# Sheet2.net
KiCad netlist of a schematic drawn in Altium Designer
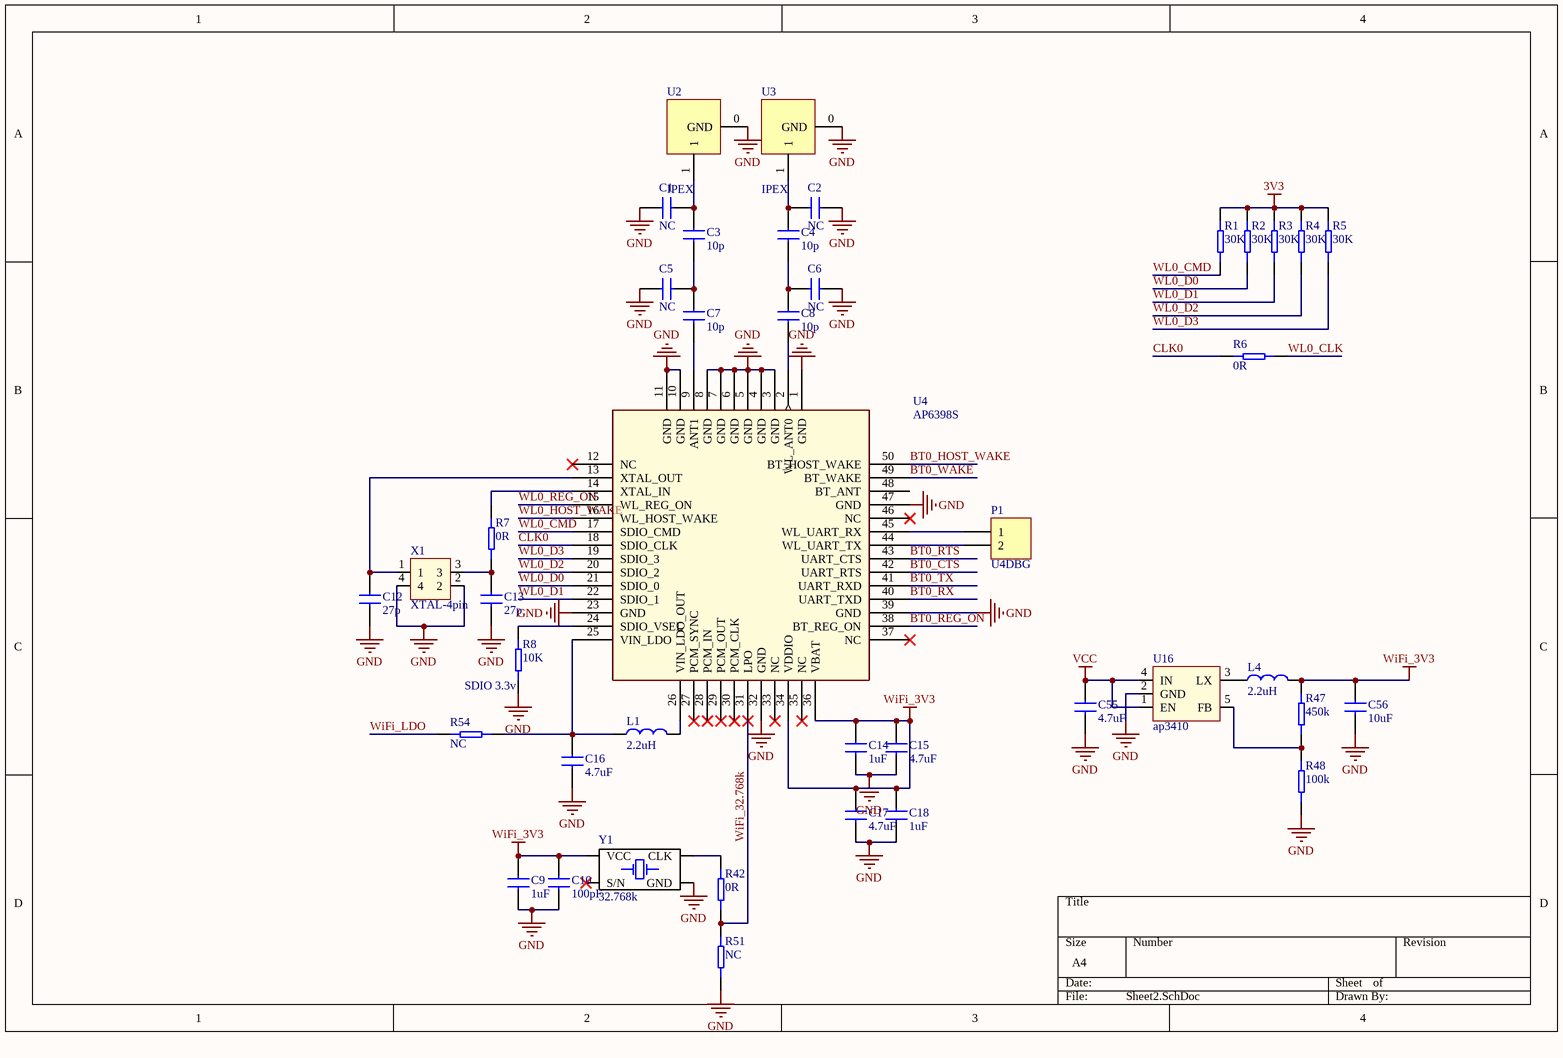
[diagram p0: Sheet2.SchDoc]

(export (version "E")
  (design (tool "Eeschema 10.0.6"))
  (components
    (comp (ref "C1")
      (value "NC")
      (footprint "0402C")
      (description "SMD-CAP")
      (libsource (lib "Zero") (part "CAP"))
    )
    (comp (ref "C2")
      (value "NC")
      (footprint "0402C")
      (description "SMD-CAP")
      (libsource (lib "Zero") (part "CAP"))
    )
    (comp (ref "C3")
      (value "10p")
      (footprint "0402C")
      (description "SMD-CAP")
      (libsource (lib "Zero") (part "CAP"))
    )
    (comp (ref "C4")
      (value "10p")
      (footprint "0402C")
      (description "SMD-CAP")
      (libsource (lib "Zero") (part "CAP"))
    )
    (comp (ref "C5")
      (value "NC")
      (footprint "0402C")
      (description "SMD-CAP")
      (libsource (lib "Zero") (part "CAP"))
    )
    (comp (ref "C6")
      (value "NC")
      (footprint "0402C")
      (description "SMD-CAP")
      (libsource (lib "Zero") (part "CAP"))
    )
    (comp (ref "C7")
      (value "10p")
      (footprint "0402C")
      (description "SMD-CAP")
      (libsource (lib "Zero") (part "CAP"))
    )
    (comp (ref "C8")
      (value "10p")
      (footprint "0402C")
      (description "SMD-CAP")
      (libsource (lib "Zero") (part "CAP"))
    )
    (comp (ref "C9")
      (value "1uF")
      (footprint "0402C")
      (description "SMD-CAP")
      (libsource (lib "Zero") (part "CAP"))
    )
    (comp (ref "C10")
      (value "100pF")
      (footprint "0402C")
      (description "SMD-CAP")
      (libsource (lib "Zero") (part "CAP"))
    )
    (comp (ref "C12")
      (value "27p")
      (footprint "0402C")
      (description "SMD-CAP")
      (libsource (lib "Zero") (part "CAP"))
    )
    (comp (ref "C13")
      (value "27p")
      (footprint "0402C")
      (description "SMD-CAP")
      (libsource (lib "Zero") (part "CAP"))
    )
    (comp (ref "C14")
      (value "1uF")
      (footprint "0402C")
      (description "SMD-CAP")
      (libsource (lib "Zero") (part "CAP"))
    )
    (comp (ref "C15")
      (value "4.7uF")
      (footprint "0402C")
      (description "SMD-CAP")
      (libsource (lib "Zero") (part "CAP"))
    )
    (comp (ref "C16")
      (value "4.7uF")
      (footprint "0603C")
      (description "SMD-CAP")
      (libsource (lib "Zero") (part "CAP"))
    )
    (comp (ref "C17")
      (value "4.7uF")
      (footprint "0402C")
      (description "SMD-CAP")
      (libsource (lib "Zero") (part "CAP"))
    )
    (comp (ref "C18")
      (value "1uF")
      (footprint "0402C")
      (description "SMD-CAP")
      (libsource (lib "Zero") (part "CAP"))
    )
    (comp (ref "C55")
      (value "4.7uF")
      (footprint "0603C")
      (description "SMD-CAP")
      (libsource (lib "Zero") (part "CAP"))
    )
    (comp (ref "C56")
      (value "10uF")
      (footprint "0603C")
      (description "SMD-CAP")
      (libsource (lib "Zero") (part "CAP"))
    )
    (comp (ref "L1")
      (value "2.2uH")
      (footprint "0805R")
      (description "LQM2MPN2R2NG0L")
      (libsource (lib "Zero") (part "L1"))
    )
    (comp (ref "L4")
      (value "2.2uH")
      (footprint "0805R")
      (description "LQM2MPN3R3NG0L")
      (libsource (lib "Zero") (part "L1"))
    )
    (comp (ref "P1")
      (value "U4DBG")
      (footprint "MHDR1X2")
      (description "Header, 2-Pin")
      (fields (field (name "PUBLISHER") "Altium Limited"))
      (libsource (lib "Miscellaneous Connectors") (part "MHDR1X2"))
    )
    (comp (ref "R1") (value "30K") (footprint "0402R") (libsource (lib "Zero") (part "R")))
    (comp (ref "R2") (value "30K") (footprint "0402R") (libsource (lib "Zero") (part "R")))
    (comp (ref "R3") (value "30K") (footprint "0402R") (libsource (lib "Zero") (part "R")))
    (comp (ref "R4") (value "30K") (footprint "0402R") (libsource (lib "Zero") (part "R")))
    (comp (ref "R5") (value "30K") (footprint "0402R") (libsource (lib "Zero") (part "R")))
    (comp (ref "R6") (value "0R") (footprint "0402R") (libsource (lib "Zero") (part "R")))
    (comp (ref "R7") (value "0R") (footprint "0402R") (libsource (lib "Zero") (part "R")))
    (comp (ref "R8") (value "10K") (footprint "0402R") (libsource (lib "Zero") (part "R")))
    (comp (ref "R42") (value "0R") (footprint "0402R") (libsource (lib "Zero") (part "R")))
    (comp (ref "R47") (value "450k") (footprint "0402R") (libsource (lib "Zero") (part "R")))
    (comp (ref "R48") (value "100k") (footprint "0402R") (libsource (lib "Zero") (part "R")))
    (comp (ref "R51") (value "NC") (footprint "0402R") (libsource (lib "Zero") (part "R")))
    (comp (ref "R54") (value "NC") (footprint "0805R") (libsource (lib "Zero") (part "R")))
    (comp (ref "U2") (value "IPEX") (footprint "IPEX") (libsource (lib "Zero") (part "IPEX")))
    (comp (ref "U3") (value "IPEX") (footprint "IPEX") (libsource (lib "Zero") (part "IPEX")))
    (comp (ref "U4")
      (value "AP6398S")
      (footprint "ap6398sr3")
      (libsource (lib "20180125H1") (part "AP6398S"))
    )
    (comp (ref "U16")
      (value "ap3410")
      (footprint "LC-SOT-23-5")
      (libsource (lib "20180125H1") (part "ap3410"))
    )
    (comp (ref "X1")
      (value "XTAL-4pin")
      (footprint "LC-SMD-3225_4P")
      (description "37.4MHz")
      (libsource (lib "20180125H1") (part "XTAL-4pin"))
    )
    (comp (ref "Y1")
      (value "32.768k")
      (footprint "3225")
      (description "3225 有源")
      (libsource (lib "常用原件库") (part "XATL1"))
    )
  )
  (nets
    (net (code "1") (name "/BT0_CTS") (class "Default")
      (node (ref "U4") (pin "42") (pinfunction "UART_RTS_42") (pintype "passive"))
    )
    (net (code "2") (name "/BT0_HOST_WAKE") (class "Default")
      (node (ref "U4") (pin "50") (pinfunction "BT_HOST_WAKE_50") (pintype "passive"))
    )
    (net (code "3") (name "/BT0_REG_ON") (class "Default")
      (node (ref "U4") (pin "38") (pinfunction "BT_REG_ON_38") (pintype "passive"))
    )
    (net (code "4") (name "/BT0_RTS") (class "Default")
      (node (ref "U4") (pin "43") (pinfunction "UART_CTS_43") (pintype "passive"))
    )
    (net (code "5") (name "/BT0_RX") (class "Default")
      (node (ref "U4") (pin "40") (pinfunction "UART_TXD_40") (pintype "passive"))
    )
    (net (code "6") (name "/BT0_TX") (class "Default")
      (node (ref "U4") (pin "41") (pinfunction "UART_RXD_41") (pintype "passive"))
    )
    (net (code "7") (name "/BT0_WAKE") (class "Default")
      (node (ref "U4") (pin "49") (pinfunction "BT_WAKE_49") (pintype "passive"))
    )
    (net (code "8") (name "/CLK0") (class "Default")
      (node (ref "R6") (pin "2") (pinfunction "2_2") (pintype "passive"))
      (node (ref "U4") (pin "18") (pinfunction "SDIO_CLK_18") (pintype "passive"))
    )
    (net (code "9") (name "/WL0_CLK") (class "Default")
      (node (ref "R6") (pin "1") (pinfunction "1_1") (pintype "passive"))
    )
    (net (code "10") (name "/WL0_CMD") (class "Default")
      (node (ref "R1") (pin "1") (pinfunction "1_1") (pintype "passive"))
      (node (ref "U4") (pin "17") (pinfunction "SDIO_CMD_17") (pintype "passive"))
    )
    (net (code "11") (name "/WL0_D0") (class "Default")
      (node (ref "R2") (pin "1") (pinfunction "1_1") (pintype "passive"))
      (node (ref "U4") (pin "21") (pinfunction "SDIO_0_21") (pintype "passive"))
    )
    (net (code "12") (name "/WL0_D1") (class "Default")
      (node (ref "R3") (pin "1") (pinfunction "1_1") (pintype "passive"))
      (node (ref "U4") (pin "22") (pinfunction "SDIO_1_22") (pintype "passive"))
    )
    (net (code "13") (name "/WL0_D2") (class "Default")
      (node (ref "R4") (pin "1") (pinfunction "1_1") (pintype "passive"))
      (node (ref "U4") (pin "20") (pinfunction "SDIO_2_20") (pintype "passive"))
    )
    (net (code "14") (name "/WL0_D3") (class "Default")
      (node (ref "R5") (pin "1") (pinfunction "1_1") (pintype "passive"))
      (node (ref "U4") (pin "19") (pinfunction "SDIO_3_19") (pintype "passive"))
    )
    (net (code "15") (name "/WL0_HOST_WAKE") (class "Default")
      (node (ref "U4") (pin "16") (pinfunction "WL_HOST_WAKE_16") (pintype "passive"))
    )
    (net (code "16") (name "/WL0_REG_ON") (class "Default")
      (node (ref "U4") (pin "15") (pinfunction "WL_REG_ON_15") (pintype "passive"))
    )
    (net (code "17") (name "/WiFi_32.768k") (class "Default")
      (node (ref "R42") (pin "1") (pinfunction "1_1") (pintype "passive"))
      (node (ref "R51") (pin "2") (pinfunction "2_2") (pintype "passive"))
      (node (ref "U4") (pin "31") (pinfunction "LPO_31") (pintype "passive"))
    )
    (net (code "18") (name "/WiFi_LDO") (class "Default")
      (node (ref "R54") (pin "2") (pinfunction "2_2") (pintype "passive"))
    )
    (net (code "19") (name "3V3") (class "Default")
      (node (ref "R1") (pin "2") (pinfunction "2_2") (pintype "passive"))
      (node (ref "R2") (pin "2") (pinfunction "2_2") (pintype "passive"))
      (node (ref "R3") (pin "2") (pinfunction "2_2") (pintype "passive"))
      (node (ref "R4") (pin "2") (pinfunction "2_2") (pintype "passive"))
      (node (ref "R5") (pin "2") (pinfunction "2_2") (pintype "passive"))
    )
    (net (code "20") (name "GND") (class "Default")
      (node (ref "C1") (pin "1") (pinfunction "1_1") (pintype "passive"))
      (node (ref "C10") (pin "2") (pinfunction "2_2") (pintype "passive"))
      (node (ref "C12") (pin "2") (pinfunction "2_2") (pintype "passive"))
      (node (ref "C13") (pin "2") (pinfunction "2_2") (pintype "passive"))
      (node (ref "C14") (pin "2") (pinfunction "2_2") (pintype "passive"))
      (node (ref "C15") (pin "2") (pinfunction "2_2") (pintype "passive"))
      (node (ref "C16") (pin "1") (pinfunction "1_1") (pintype "passive"))
      (node (ref "C17") (pin "2") (pinfunction "2_2") (pintype "passive"))
      (node (ref "C18") (pin "2") (pinfunction "2_2") (pintype "passive"))
      (node (ref "C2") (pin "2") (pinfunction "2_2") (pintype "passive"))
      (node (ref "C5") (pin "1") (pinfunction "1_1") (pintype "passive"))
      (node (ref "C55") (pin "2") (pinfunction "2_2") (pintype "passive"))
      (node (ref "C56") (pin "2") (pinfunction "2_2") (pintype "passive"))
      (node (ref "C6") (pin "2") (pinfunction "2_2") (pintype "passive"))
      (node (ref "C9") (pin "2") (pinfunction "2_2") (pintype "passive"))
      (node (ref "R48") (pin "1") (pinfunction "1_1") (pintype "passive"))
      (node (ref "R51") (pin "1") (pinfunction "1_1") (pintype "passive"))
      (node (ref "R8") (pin "1") (pinfunction "1_1") (pintype "passive"))
      (node (ref "U16") (pin "2") (pinfunction "GND_2") (pintype "passive"))
      (node (ref "U2") (pin "0") (pinfunction "GND_0") (pintype "passive"))
      (node (ref "U3") (pin "0") (pinfunction "GND_0") (pintype "passive"))
      (node (ref "U4") (pin "1") (pinfunction "GND_1") (pintype "power_in"))
      (node (ref "U4") (pin "10") (pinfunction "GND_10") (pintype "power_in"))
      (node (ref "U4") (pin "11") (pinfunction "GND_11") (pintype "power_in"))
      (node (ref "U4") (pin "23") (pinfunction "GND_23") (pintype "power_in"))
      (node (ref "U4") (pin "3") (pinfunction "GND_3") (pintype "power_in"))
      (node (ref "U4") (pin "32") (pinfunction "GND_32") (pintype "power_in"))
      (node (ref "U4") (pin "39") (pinfunction "GND_39") (pintype "power_in"))
      (node (ref "U4") (pin "4") (pinfunction "GND_4") (pintype "power_in"))
      (node (ref "U4") (pin "47") (pinfunction "GND_47") (pintype "passive"))
      (node (ref "U4") (pin "5") (pinfunction "GND_5") (pintype "power_in"))
      (node (ref "U4") (pin "6") (pinfunction "GND_6") (pintype "power_in"))
      (node (ref "U4") (pin "7") (pinfunction "GND_7") (pintype "power_in"))
      (node (ref "U4") (pin "8") (pinfunction "GND_8") (pintype "power_in"))
      (node (ref "X1") (pin "2") (pinfunction "2_2") (pintype "passive"))
      (node (ref "X1") (pin "4") (pinfunction "4_4") (pintype "passive"))
      (node (ref "Y1") (pin "2") (pinfunction "GND_2") (pintype "passive"))
    )
    (net (code "21") (name "Net-(C1-Pad2)") (class "Default")
      (node (ref "C1") (pin "2") (pinfunction "2_2") (pintype "passive"))
      (node (ref "C3") (pin "2") (pinfunction "2_2") (pintype "passive"))
      (node (ref "U2") (pin "1") (pinfunction "1_1") (pintype "passive"))
    )
    (net (code "22") (name "Net-(C2-Pad1)") (class "Default")
      (node (ref "C2") (pin "1") (pinfunction "1_1") (pintype "passive"))
      (node (ref "C4") (pin "1") (pinfunction "1_1") (pintype "passive"))
      (node (ref "U3") (pin "1") (pinfunction "1_1") (pintype "passive"))
    )
    (net (code "23") (name "Net-(C3-Pad1)") (class "Default")
      (node (ref "C3") (pin "1") (pinfunction "1_1") (pintype "passive"))
      (node (ref "C5") (pin "2") (pinfunction "2_2") (pintype "passive"))
      (node (ref "C7") (pin "1") (pinfunction "1_1") (pintype "passive"))
    )
    (net (code "24") (name "Net-(C4-Pad2)") (class "Default")
      (node (ref "C4") (pin "2") (pinfunction "2_2") (pintype "passive"))
      (node (ref "C6") (pin "1") (pinfunction "1_1") (pintype "passive"))
      (node (ref "C8") (pin "1") (pinfunction "1_1") (pintype "passive"))
    )
    (net (code "25") (name "Net-(C13-Pad1)") (class "Default")
      (node (ref "C13") (pin "1") (pinfunction "1_1") (pintype "passive"))
      (node (ref "R7") (pin "1") (pinfunction "1_1") (pintype "passive"))
      (node (ref "X1") (pin "3") (pinfunction "3_3") (pintype "passive"))
    )
    (net (code "26") (name "Net-(U4-ANT1)") (class "Default")
      (node (ref "C7") (pin "2") (pinfunction "2_2") (pintype "passive"))
      (node (ref "U4") (pin "9") (pinfunction "ANT1_9") (pintype "power_in"))
    )
    (net (code "27") (name "Net-(U4-SDIO_VSEL)") (class "Default")
      (node (ref "R8") (pin "2") (pinfunction "2_2") (pintype "passive"))
      (node (ref "U4") (pin "24") (pinfunction "SDIO_VSEL_24") (pintype "passive"))
    )
    (net (code "28") (name "Net-(U4-VIN_LDO)") (class "Default")
      (node (ref "C16") (pin "2") (pinfunction "2_2") (pintype "passive"))
      (node (ref "L1") (pin "2") (pinfunction "2_2") (pintype "passive"))
      (node (ref "R54") (pin "1") (pinfunction "1_1") (pintype "passive"))
      (node (ref "U4") (pin "25") (pinfunction "VIN_LDO_25") (pintype "passive"))
    )
    (net (code "29") (name "Net-(U4-VIN_LDO_OUT)") (class "Default")
      (node (ref "L1") (pin "1") (pinfunction "1_1") (pintype "passive"))
      (node (ref "U4") (pin "26") (pinfunction "VIN_LDO_OUT_26") (pintype "passive"))
    )
    (net (code "30") (name "Net-(U4-WL_ANT0)") (class "Default")
      (node (ref "C8") (pin "2") (pinfunction "2_2") (pintype "passive"))
      (node (ref "U4") (pin "2") (pinfunction "WL_ANT0_2") (pintype "output"))
    )
    (net (code "31") (name "Net-(U4-WL_UART_RX)") (class "Default")
      (node (ref "P1") (pin "1") (pinfunction "1_1") (pintype "passive"))
      (node (ref "U4") (pin "45") (pinfunction "WL_UART_RX_45") (pintype "passive"))
    )
    (net (code "32") (name "Net-(U4-WL_UART_TX)") (class "Default")
      (node (ref "P1") (pin "2") (pinfunction "2_2") (pintype "passive"))
      (node (ref "U4") (pin "44") (pinfunction "WL_UART_TX_44") (pintype "passive"))
    )
    (net (code "33") (name "Net-(U4-XTAL_IN)") (class "Default")
      (node (ref "R7") (pin "2") (pinfunction "2_2") (pintype "passive"))
      (node (ref "U4") (pin "14") (pinfunction "XTAL_IN_14") (pintype "passive"))
    )
    (net (code "34") (name "Net-(U4-XTAL_OUT)") (class "Default")
      (node (ref "C12") (pin "1") (pinfunction "1_1") (pintype "passive"))
      (node (ref "U4") (pin "13") (pinfunction "XTAL_OUT_13") (pintype "passive"))
      (node (ref "X1") (pin "1") (pinfunction "1_1") (pintype "passive"))
    )
    (net (code "35") (name "Net-(U16-FB)") (class "Default")
      (node (ref "R47") (pin "1") (pinfunction "1_1") (pintype "passive"))
      (node (ref "R48") (pin "2") (pinfunction "2_2") (pintype "passive"))
      (node (ref "U16") (pin "5") (pinfunction "FB_5") (pintype "passive"))
    )
    (net (code "36") (name "Net-(U16-LX)") (class "Default")
      (node (ref "L4") (pin "2") (pinfunction "2_2") (pintype "passive"))
      (node (ref "U16") (pin "3") (pinfunction "LX_3") (pintype "passive"))
    )
    (net (code "37") (name "Net-(Y1-CLK)") (class "Default")
      (node (ref "R42") (pin "2") (pinfunction "2_2") (pintype "passive"))
      (node (ref "Y1") (pin "3") (pinfunction "CLK_3") (pintype "passive"))
    )
    (net (code "38") (name "VCC") (class "Default")
      (node (ref "C55") (pin "1") (pinfunction "1_1") (pintype "passive"))
      (node (ref "U16") (pin "1") (pinfunction "EN_1") (pintype "passive"))
      (node (ref "U16") (pin "4") (pinfunction "IN_4") (pintype "passive"))
    )
    (net (code "39") (name "WiFi_3V3") (class "Default")
      (node (ref "C10") (pin "1") (pinfunction "1_1") (pintype "passive"))
      (node (ref "C14") (pin "1") (pinfunction "1_1") (pintype "passive"))
      (node (ref "C15") (pin "1") (pinfunction "1_1") (pintype "passive"))
      (node (ref "C17") (pin "1") (pinfunction "1_1") (pintype "passive"))
      (node (ref "C18") (pin "1") (pinfunction "1_1") (pintype "passive"))
      (node (ref "C56") (pin "1") (pinfunction "1_1") (pintype "passive"))
      (node (ref "C9") (pin "1") (pinfunction "1_1") (pintype "passive"))
      (node (ref "L4") (pin "1") (pinfunction "1_1") (pintype "passive"))
      (node (ref "R47") (pin "2") (pinfunction "2_2") (pintype "passive"))
      (node (ref "U4") (pin "34") (pinfunction "VDDIO_34") (pintype "passive"))
      (node (ref "U4") (pin "36") (pinfunction "VBAT_36") (pintype "passive"))
      (node (ref "Y1") (pin "4") (pinfunction "VCC_4") (pintype "passive"))
    )
    (net (code "40") (name "unconnected-(U4-BT_ANT-Pad48)") (class "Default")
      (node (ref "U4") (pin "48") (pinfunction "BT_ANT_48") (pintype "passive"))
    )
    (net (code "41") (name "unconnected-(U4-NC-Pad12)") (class "Default")
      (node (ref "U4") (pin "12") (pinfunction "NC_12") (pintype "passive+no_connect"))
    )
    (net (code "42") (name "unconnected-(U4-NC-Pad33)") (class "Default")
      (node (ref "U4") (pin "33") (pinfunction "NC_33") (pintype "passive+no_connect"))
    )
    (net (code "43") (name "unconnected-(U4-NC-Pad35)") (class "Default")
      (node (ref "U4") (pin "35") (pinfunction "NC_35") (pintype "passive+no_connect"))
    )
    (net (code "44") (name "unconnected-(U4-NC-Pad37)") (class "Default")
      (node (ref "U4") (pin "37") (pinfunction "NC_37") (pintype "passive+no_connect"))
    )
    (net (code "45") (name "unconnected-(U4-NC-Pad46)") (class "Default")
      (node (ref "U4") (pin "46") (pinfunction "NC_46") (pintype "passive+no_connect"))
    )
    (net (code "46") (name "unconnected-(U4-PCM_CLK-Pad30)") (class "Default")
      (node (ref "U4") (pin "30") (pinfunction "PCM_CLK_30") (pintype "passive+no_connect"))
    )
    (net (code "47") (name "unconnected-(U4-PCM_IN-Pad28)") (class "Default")
      (node (ref "U4") (pin "28") (pinfunction "PCM_IN_28") (pintype "passive+no_connect"))
    )
    (net (code "48") (name "unconnected-(U4-PCM_OUT-Pad29)") (class "Default")
      (node (ref "U4") (pin "29") (pinfunction "PCM_OUT_29") (pintype "passive+no_connect"))
    )
    (net (code "49") (name "unconnected-(U4-PCM_SYNC-Pad27)") (class "Default")
      (node (ref "U4") (pin "27") (pinfunction "PCM_SYNC_27") (pintype "passive+no_connect"))
    )
    (net (code "50") (name "unconnected-(Y1-S{slash}N-Pad1)") (class "Default")
      (node (ref "Y1") (pin "1") (pinfunction "S/N_1") (pintype "passive+no_connect"))
    )
  )
)
